# servo-actuator.net
KiCad netlist of a schematic drawn in EAGLE
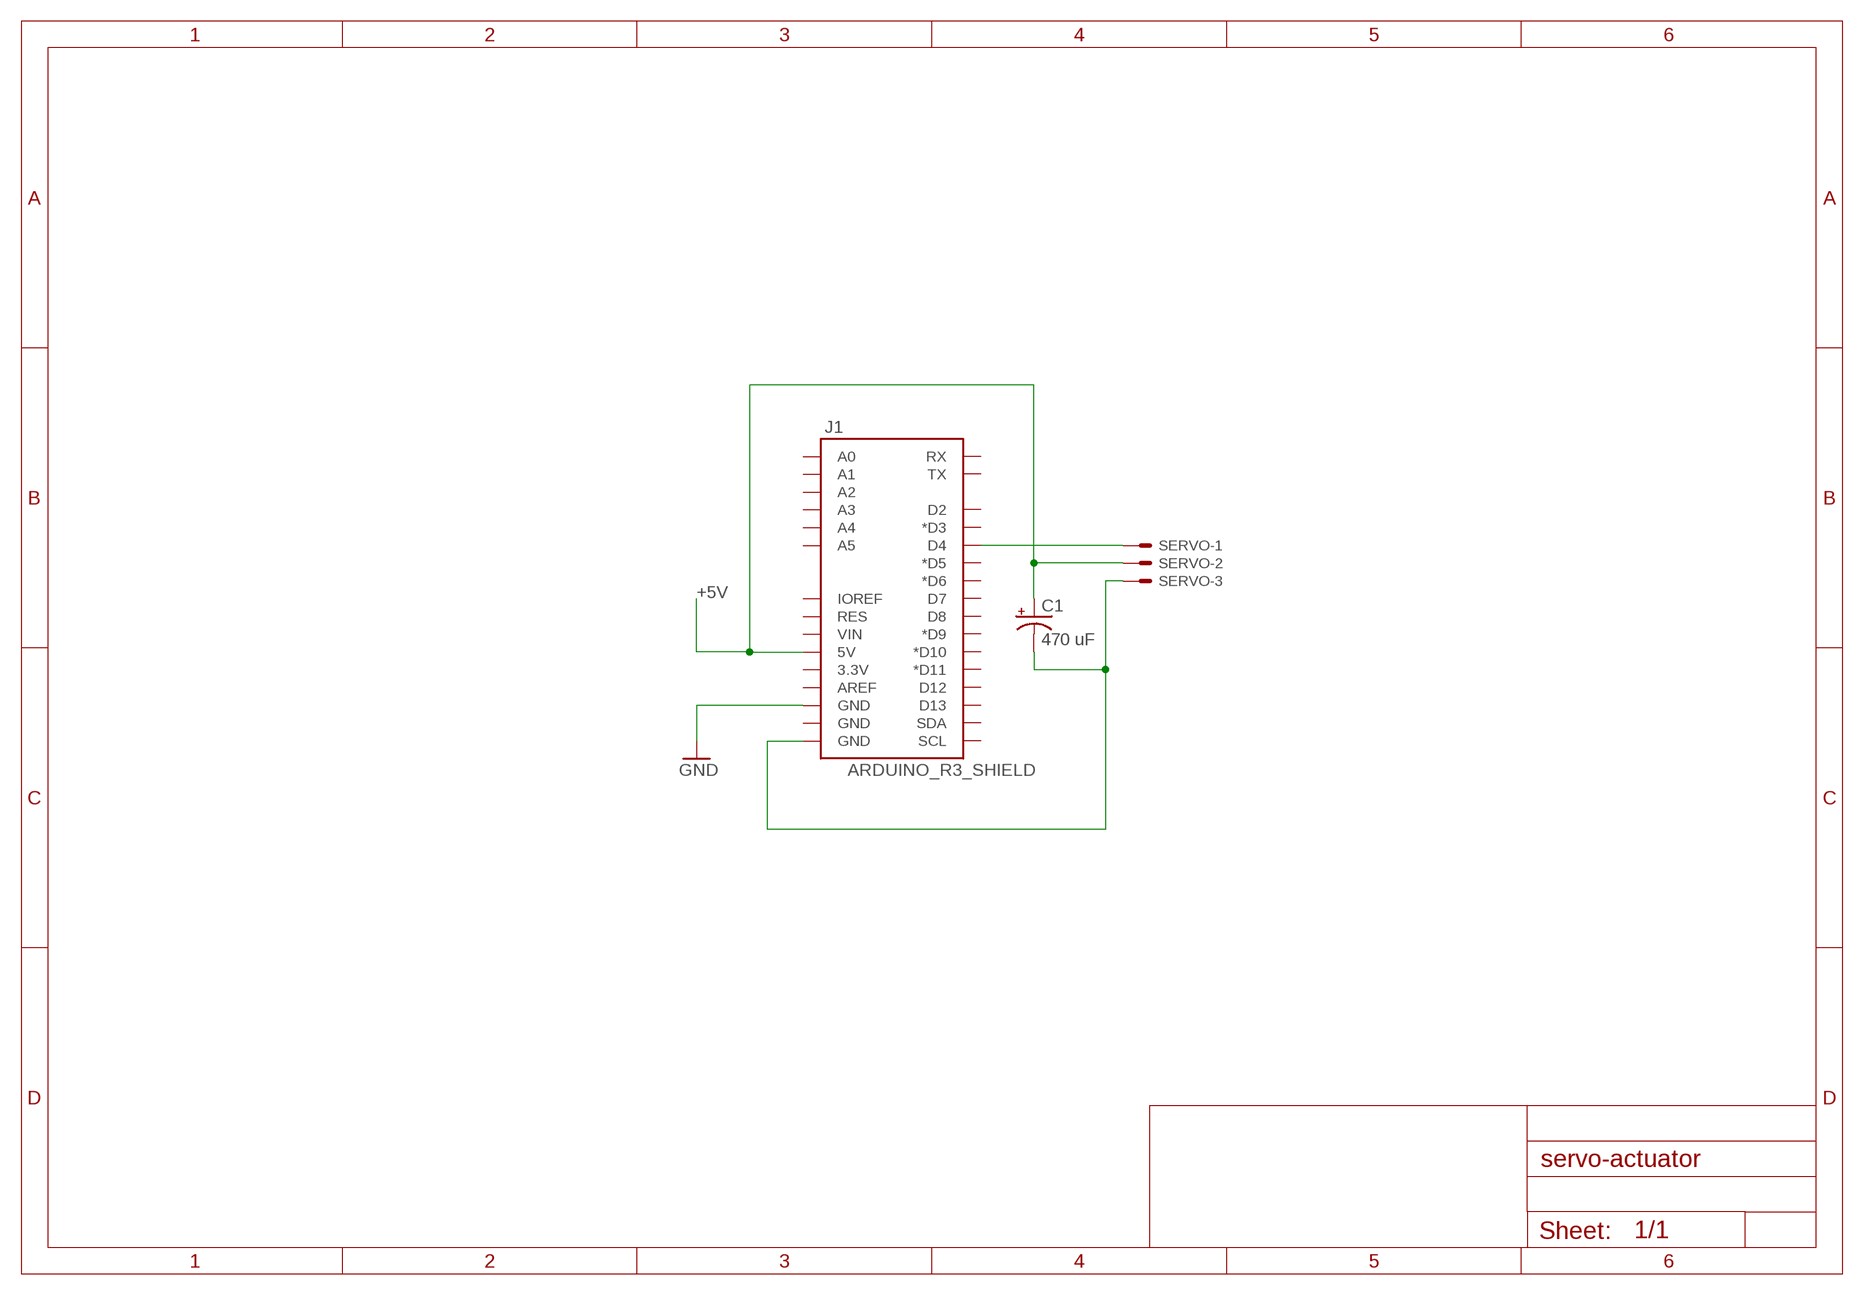
[diagram p0: schematic, sheet 1]

(export (version "E")
  (design (tool "Eeschema 10.0.6"))
  (components
    (comp (ref "C1")
      (value "470 uF")
      (footprint "eagle-import:EIA3216")
      (libsource (lib "eagle-import") (part "CAP_POL1206"))
    )
    (comp (ref "J1")
      (value "ARDUINO_R3_SHIELD")
      (footprint "eagle-import:UNO_R3_SHIELD")
      (libsource (lib "eagle-import") (part "ARDUINO_R3_SHIELD"))
    )
    (comp (ref "SERVO")
      (value "22-23-2031")
      (footprint "eagle-import:22-23-2031")
      (fields (field (name "MF") "MOLEX"))
      (libsource (lib "eagle-import") (part "22-23-2031"))
    )
  )
  (nets
    (net (code "1") (name "/+5V") (class "Default")
      (node (ref "C1") (pin "A") (pinfunction "+_A") (pintype "passive"))
      (node (ref "J1") (pin "5V") (pinfunction "5V_5V") (pintype "bidirectional"))
      (node (ref "SERVO") (pin "2") (pinfunction "S_2") (pintype "passive"))
    )
    (net (code "2") (name "GND") (class "Default")
      (node (ref "J1") (pin "GND@2") (pinfunction "GND_GND@2") (pintype "bidirectional"))
    )
    (net (code "3") (name "Net-(C1--)") (class "Default")
      (node (ref "C1") (pin "C") (pinfunction "-_C") (pintype "passive"))
      (node (ref "J1") (pin "GND@0") (pinfunction "GND_GND@0") (pintype "bidirectional"))
      (node (ref "SERVO") (pin "3") (pinfunction "S_3") (pintype "passive"))
    )
    (net (code "4") (name "Net-(SERVOA-S)") (class "Default")
      (node (ref "J1") (pin "D4") (pinfunction "D4_D4") (pintype "bidirectional"))
      (node (ref "SERVO") (pin "1") (pinfunction "S_1") (pintype "passive"))
    )
    (net (code "5") (name "unconnected-(J1-*D3-PadD3)") (class "Default")
      (node (ref "J1") (pin "D3") (pinfunction "*D3_D3") (pintype "bidirectional"))
    )
    (net (code "6") (name "unconnected-(J1-*D5-PadD5)") (class "Default")
      (node (ref "J1") (pin "D5") (pinfunction "*D5_D5") (pintype "bidirectional"))
    )
    (net (code "7") (name "unconnected-(J1-*D6-PadD6)") (class "Default")
      (node (ref "J1") (pin "D6") (pinfunction "*D6_D6") (pintype "bidirectional"))
    )
    (net (code "8") (name "unconnected-(J1-*D9-PadD9)") (class "Default")
      (node (ref "J1") (pin "D9") (pinfunction "*D9_D9") (pintype "bidirectional"))
    )
    (net (code "9") (name "unconnected-(J1-*D10-PadD10)") (class "Default")
      (node (ref "J1") (pin "D10") (pinfunction "*D10_D10") (pintype "bidirectional"))
    )
    (net (code "10") (name "unconnected-(J1-*D11-PadD11)") (class "Default")
      (node (ref "J1") (pin "D11") (pinfunction "*D11_D11") (pintype "bidirectional"))
    )
    (net (code "11") (name "unconnected-(J1-GND-PadGND@1)") (class "Default")
      (node (ref "J1") (pin "GND@1") (pinfunction "GND_GND@1") (pintype "bidirectional"))
    )
    (net (code "12") (name "unconnected-(J1-Pad3.3V)") (class "Default")
      (node (ref "J1") (pin "3.3V") (pinfunction "3.3V_3.3V") (pintype "bidirectional"))
    )
    (net (code "13") (name "unconnected-(J1-PadA0)") (class "Default")
      (node (ref "J1") (pin "A0") (pinfunction "A0_A0") (pintype "bidirectional"))
    )
    (net (code "14") (name "unconnected-(J1-PadA1)") (class "Default")
      (node (ref "J1") (pin "A1") (pinfunction "A1_A1") (pintype "bidirectional"))
    )
    (net (code "15") (name "unconnected-(J1-PadA2)") (class "Default")
      (node (ref "J1") (pin "A2") (pinfunction "A2_A2") (pintype "bidirectional"))
    )
    (net (code "16") (name "unconnected-(J1-PadA3)") (class "Default")
      (node (ref "J1") (pin "A3") (pinfunction "A3_A3") (pintype "bidirectional"))
    )
    (net (code "17") (name "unconnected-(J1-PadA4)") (class "Default")
      (node (ref "J1") (pin "A4") (pinfunction "A4_A4") (pintype "bidirectional"))
    )
    (net (code "18") (name "unconnected-(J1-PadA5)") (class "Default")
      (node (ref "J1") (pin "A5") (pinfunction "A5_A5") (pintype "bidirectional"))
    )
    (net (code "19") (name "unconnected-(J1-PadAREF)") (class "Default")
      (node (ref "J1") (pin "AREF") (pinfunction "AREF_AREF") (pintype "bidirectional"))
    )
    (net (code "20") (name "unconnected-(J1-PadD2)") (class "Default")
      (node (ref "J1") (pin "D2") (pinfunction "D2_D2") (pintype "bidirectional"))
    )
    (net (code "21") (name "unconnected-(J1-PadD7)") (class "Default")
      (node (ref "J1") (pin "D7") (pinfunction "D7_D7") (pintype "bidirectional"))
    )
    (net (code "22") (name "unconnected-(J1-PadD8)") (class "Default")
      (node (ref "J1") (pin "D8") (pinfunction "D8_D8") (pintype "bidirectional"))
    )
    (net (code "23") (name "unconnected-(J1-PadD12)") (class "Default")
      (node (ref "J1") (pin "D12") (pinfunction "D12_D12") (pintype "bidirectional"))
    )
    (net (code "24") (name "unconnected-(J1-PadD13)") (class "Default")
      (node (ref "J1") (pin "D13") (pinfunction "D13_D13") (pintype "bidirectional"))
    )
    (net (code "25") (name "unconnected-(J1-PadIOREF)") (class "Default")
      (node (ref "J1") (pin "IOREF") (pinfunction "IOREF_IOREF") (pintype "bidirectional"))
    )
    (net (code "26") (name "unconnected-(J1-PadRES)") (class "Default")
      (node (ref "J1") (pin "RES") (pinfunction "RES_RES") (pintype "bidirectional"))
    )
    (net (code "27") (name "unconnected-(J1-PadRX)") (class "Default")
      (node (ref "J1") (pin "RX") (pinfunction "RX_RX") (pintype "bidirectional"))
    )
    (net (code "28") (name "unconnected-(J1-PadSCL)") (class "Default")
      (node (ref "J1") (pin "SCL") (pinfunction "SCL_SCL") (pintype "bidirectional"))
    )
    (net (code "29") (name "unconnected-(J1-PadSDA)") (class "Default")
      (node (ref "J1") (pin "SDA") (pinfunction "SDA_SDA") (pintype "bidirectional"))
    )
    (net (code "30") (name "unconnected-(J1-PadTX)") (class "Default")
      (node (ref "J1") (pin "TX") (pinfunction "TX_TX") (pintype "bidirectional"))
    )
    (net (code "31") (name "unconnected-(J1-PadVIN)") (class "Default")
      (node (ref "J1") (pin "VIN") (pinfunction "VIN_VIN") (pintype "bidirectional"))
    )
  )
)
